# SSTuino.net
KiCad netlist of a schematic drawn in EAGLE
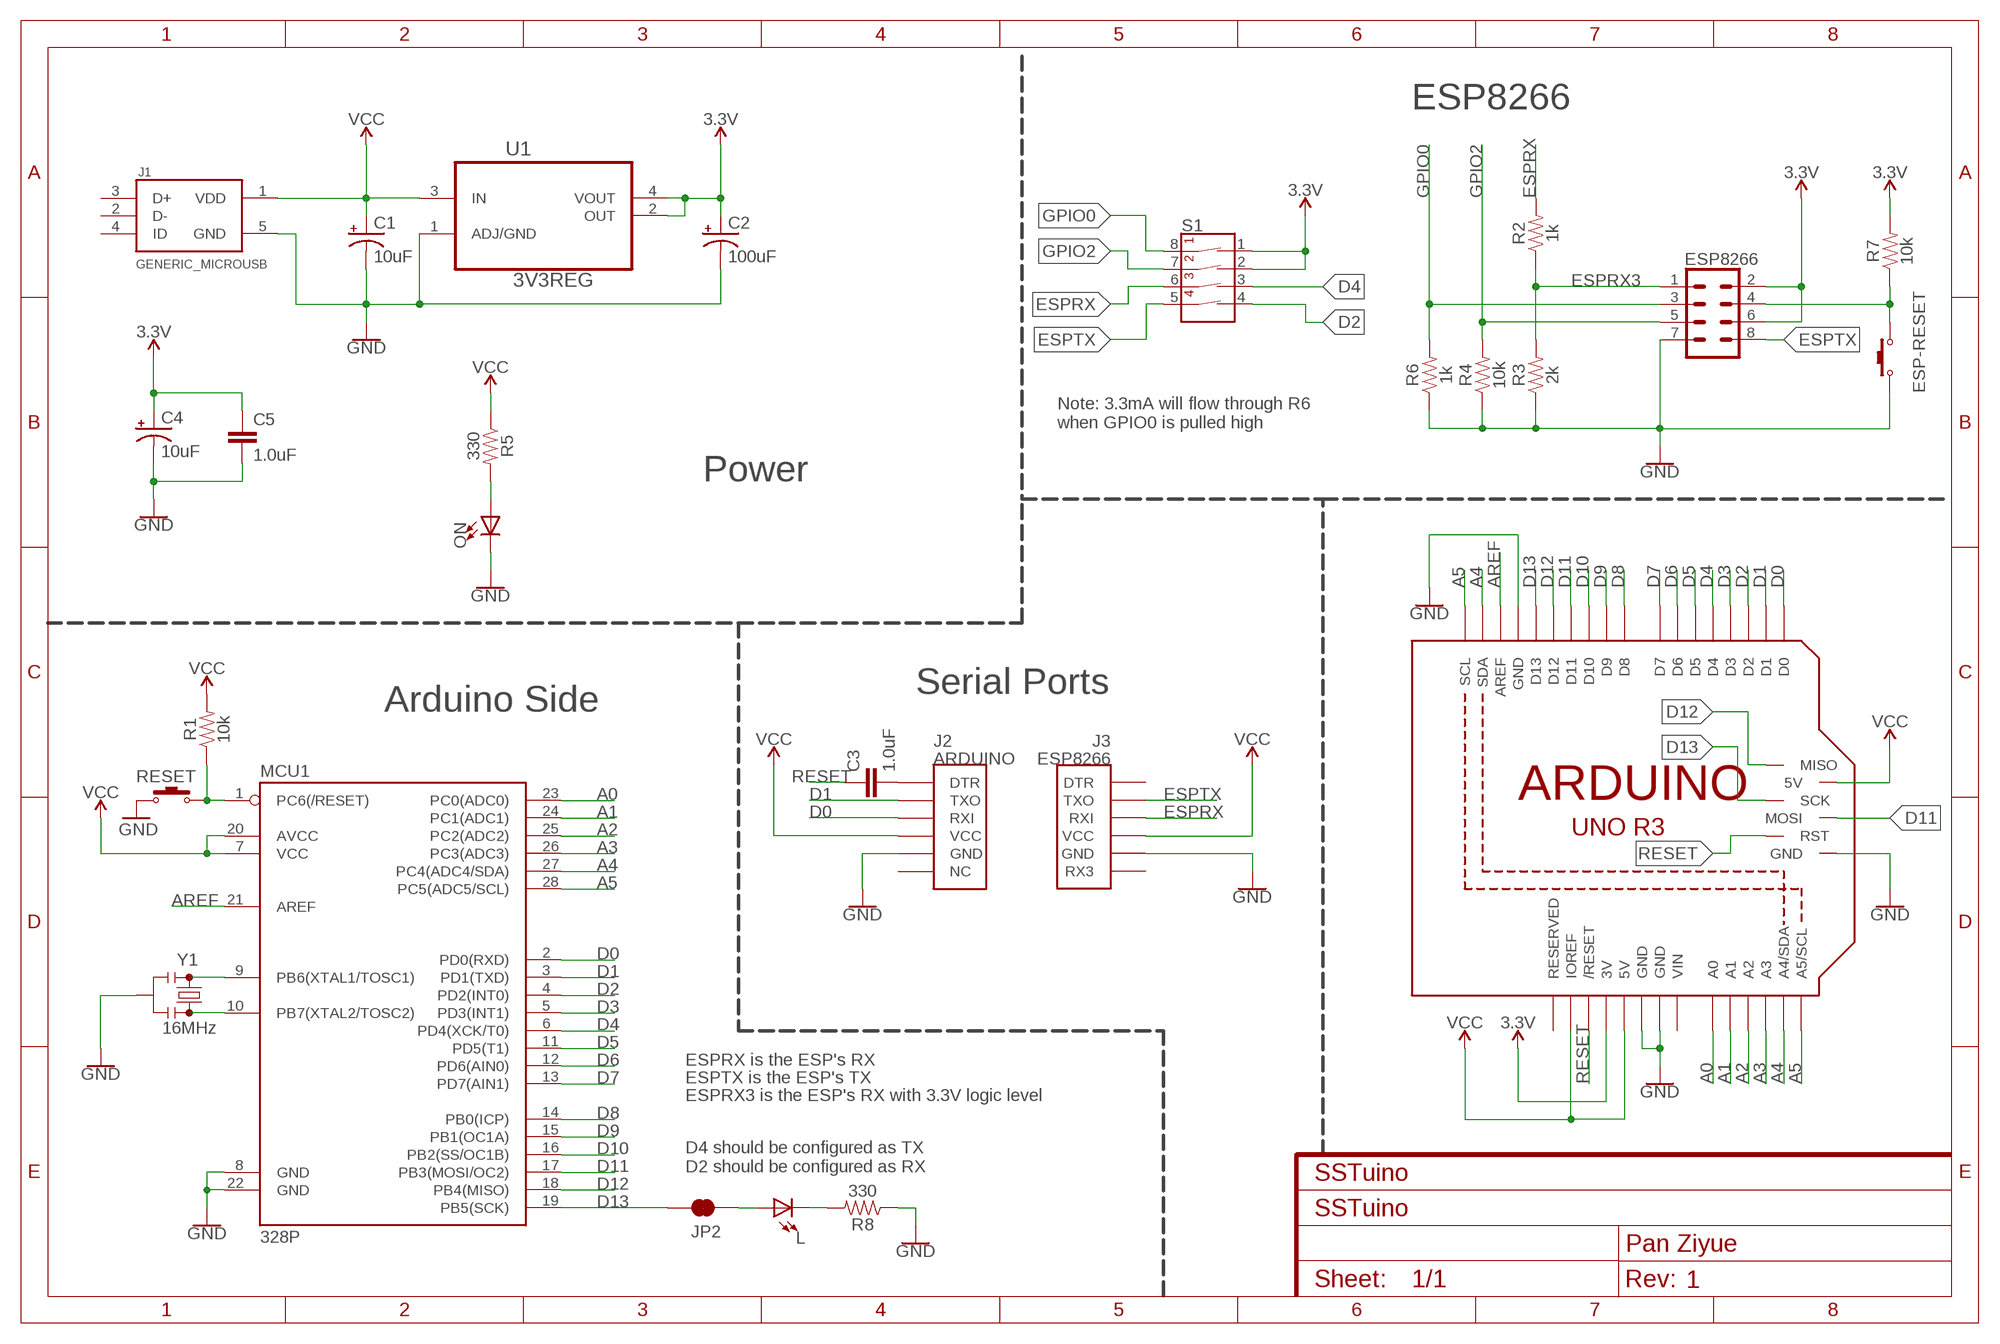
[diagram p0: schematic, sheet 1]

(export (version "E")
  (design (tool "Eeschema 10.0.6"))
  (components
    (comp (ref "C1")
      (value "10uF")
      (footprint "eagle-import:EIA3528")
      (libsource (lib "eagle-import") (part "10UF-POLAR-EIA3528-20V-10%(TANT)"))
    )
    (comp (ref "C2")
      (value "100uF")
      (footprint "eagle-import:PANASONIC_D")
      (libsource (lib "eagle-import") (part "100UF-POLAR-25V-20%(ELEC)"))
    )
    (comp (ref "C3")
      (value "1.0uF")
      (footprint "eagle-import:1206")
      (libsource (lib "eagle-import") (part "1.0UF-1206-50V-10%"))
    )
    (comp (ref "C4")
      (value "10uF")
      (footprint "eagle-import:EIA3216")
      (libsource (lib "eagle-import") (part "10UF-POLAR-EIA3216-16V-10%(TANT)"))
    )
    (comp (ref "C5")
      (value "1.0uF")
      (footprint "eagle-import:1206")
      (fields (field (name "SPICEPREFIX") "C"))
      (libsource (lib "eagle-import") (part "1.0UF-1206-50V-10%"))
    )
    (comp (ref "ESP-RESET")
      (value "SW-PB_(KAN0641)")
      (footprint "eagle-import:S-SP-4N-KAN0641")
      (fields (field (name "MF") "GANGYUAN") (field (name "MPN") "KAN0641-0501B1"))
      (libsource (lib "eagle-import") (part "SW-PB_(KAN0641)"))
    )
    (comp (ref "ESP8266")
      (value "CONN_04X2")
      (footprint "eagle-import:2X4")
      (libsource (lib "eagle-import") (part "CONN_04X2"))
    )
    (comp (ref "J1")
      (value "GENERIC_MICROUSB")
      (footprint "eagle-import:FRAMATOME_10118194-0001LF")
      (fields (field (name "MF") "FCI") (field (name "MP") "10118194-0001LF"))
      (libsource (lib "eagle-import") (part "GENERIC_MICROUSB"))
    )
    (comp (ref "J2")
      (value "ARDUINO")
      (footprint "eagle-import:CP2102_DEVICE_MICROUSB")
      (libsource (lib "eagle-import") (part "CP2102_DEVICEMICROUSB"))
    )
    (comp (ref "J3")
      (value "ESP8266")
      (footprint "eagle-import:CP2102_DEVICE_MICROUSB_ESP8266")
      (libsource (lib "eagle-import") (part "CP2102_DEVICE_ESP8266"))
    )
    (comp (ref "JP2")
      (value "JUMPER-SMT_2_NC_TRACE_SILK")
      (footprint "eagle-import:SMT-JUMPER_2_NC_TRACE_SILK")
      (libsource (lib "eagle-import") (part "JUMPER-SMT_2_NC_TRACE_SILK"))
    )
    (comp (ref "L")
      (value "LED3MM")
      (footprint "eagle-import:LED3MM")
      (libsource (lib "eagle-import") (part "LED3MM"))
    )
    (comp (ref "M1")
      (value "ARDUINO_R3_ICSPSST")
      (footprint "eagle-import:ARDUINOR3_ISCP_SST")
      (libsource (lib "eagle-import") (part "ARDUINO_R3_ICSPSST"))
    )
    (comp (ref "MCU1")
      (value "328P")
      (footprint "eagle-import:DIP28")
      (libsource (lib "eagle-import") (part "ATMEGA328P_PDIP"))
    )
    (comp (ref "ON")
      (value "LED3MM")
      (footprint "eagle-import:LED3MM")
      (libsource (lib "eagle-import") (part "LED3MM"))
    )
    (comp (ref "R1")
      (value "10k")
      (footprint "eagle-import:1206")
      (libsource (lib "eagle-import") (part "RESISTOR1206"))
    )
    (comp (ref "R2")
      (value "1k")
      (footprint "eagle-import:1206")
      (libsource (lib "eagle-import") (part "RESISTOR1206"))
    )
    (comp (ref "R3")
      (value "2k")
      (footprint "eagle-import:1206")
      (libsource (lib "eagle-import") (part "RESISTOR1206"))
    )
    (comp (ref "R4")
      (value "10k")
      (footprint "eagle-import:1206")
      (libsource (lib "eagle-import") (part "RESISTOR1206"))
    )
    (comp (ref "R5")
      (value "330")
      (footprint "eagle-import:1206")
      (libsource (lib "eagle-import") (part "RESISTOR1206"))
    )
    (comp (ref "R6")
      (value "1k")
      (footprint "eagle-import:1206")
      (libsource (lib "eagle-import") (part "RESISTOR1206"))
    )
    (comp (ref "R7")
      (value "10k")
      (footprint "eagle-import:1206")
      (libsource (lib "eagle-import") (part "RESISTOR1206"))
    )
    (comp (ref "R8")
      (value "330")
      (footprint "eagle-import:1206")
      (libsource (lib "eagle-import") (part "RESISTOR1206"))
    )
    (comp (ref "RESET")
      (value "SW-PB_(KAN0641)")
      (footprint "eagle-import:S-SP-4N-KAN0641")
      (fields (field (name "MF") "GANGYUAN") (field (name "MPN") "KAN0641-0501B1"))
      (libsource (lib "eagle-import") (part "SW-PB_(KAN0641)"))
    )
    (comp (ref "S1")
      (value "DIP-04SMD")
      (footprint "eagle-import:DIPSWITCH-04-SMD")
      (fields (field (name "SPICEPREFIX") "X"))
      (libsource (lib "eagle-import") (part "DIP-04SMD"))
    )
    (comp (ref "U1")
      (value "3V3REG")
      (footprint "eagle-import:SOT230P696X180-4N")
      (fields (field (name "MPN") "LM1117MP-3.3"))
      (libsource (lib "eagle-import") (part "LM1117MP-3.3"))
    )
    (comp (ref "Y1")
      (value "16MHz")
      (footprint "eagle-import:RESONATOR-SMD-3.2X1.3")
      (libsource (lib "eagle-import") (part "RESONATOR-16MHZSMD_3.2X1.3"))
    )
  )
  (nets
    (net (code "1") (name "/A0") (class "Default")
      (node (ref "M1") (pin "A0") (pinfunction "A0_A0") (pintype "bidirectional"))
      (node (ref "MCU1") (pin "23") (pinfunction "PC0(ADC0)_23") (pintype "bidirectional"))
    )
    (net (code "2") (name "/A1") (class "Default")
      (node (ref "M1") (pin "A1") (pinfunction "A1_A1") (pintype "bidirectional"))
      (node (ref "MCU1") (pin "24") (pinfunction "PC1(ADC1)_24") (pintype "bidirectional"))
    )
    (net (code "3") (name "/A2") (class "Default")
      (node (ref "M1") (pin "A2") (pinfunction "A2_A2") (pintype "bidirectional"))
      (node (ref "MCU1") (pin "25") (pinfunction "PC2(ADC2)_25") (pintype "bidirectional"))
    )
    (net (code "4") (name "/A3") (class "Default")
      (node (ref "M1") (pin "A3") (pinfunction "A3_A3") (pintype "bidirectional"))
      (node (ref "MCU1") (pin "26") (pinfunction "PC3(ADC3)_26") (pintype "bidirectional"))
    )
    (net (code "5") (name "/A4") (class "Default")
      (node (ref "M1") (pin "A4") (pinfunction "A4/SDA_A4") (pintype "bidirectional"))
      (node (ref "M1") (pin "SDA") (pinfunction "SDA_SDA") (pintype "bidirectional"))
      (node (ref "MCU1") (pin "27") (pinfunction "PC4(ADC4/SDA)_27") (pintype "bidirectional"))
    )
    (net (code "6") (name "/A5") (class "Default")
      (node (ref "M1") (pin "A5") (pinfunction "A5/SCL_A5") (pintype "bidirectional"))
      (node (ref "M1") (pin "SCL") (pinfunction "SCL_SCL") (pintype "bidirectional"))
      (node (ref "MCU1") (pin "28") (pinfunction "PC5(ADC5/SCL)_28") (pintype "bidirectional"))
    )
    (net (code "7") (name "/AREF") (class "Default")
      (node (ref "M1") (pin "AREF") (pinfunction "AREF_AREF") (pintype "bidirectional"))
      (node (ref "MCU1") (pin "21") (pinfunction "AREF_21") (pintype "bidirectional"))
    )
    (net (code "8") (name "/D0") (class "Default")
      (node (ref "J2") (pin "RXI") (pinfunction "RXI_RXI") (pintype "bidirectional"))
      (node (ref "M1") (pin "D0") (pinfunction "D0_D0") (pintype "bidirectional"))
      (node (ref "MCU1") (pin "2") (pinfunction "PD0(RXD)_2") (pintype "bidirectional"))
    )
    (net (code "9") (name "/D1") (class "Default")
      (node (ref "J2") (pin "TXO") (pinfunction "TXO_TXO") (pintype "bidirectional"))
      (node (ref "M1") (pin "D1") (pinfunction "D1_D1") (pintype "bidirectional"))
      (node (ref "MCU1") (pin "3") (pinfunction "PD1(TXD)_3") (pintype "bidirectional"))
    )
    (net (code "10") (name "/D3") (class "Default")
      (node (ref "M1") (pin "D3") (pinfunction "D3_D3") (pintype "bidirectional"))
      (node (ref "MCU1") (pin "5") (pinfunction "PD3(INT1)_5") (pintype "bidirectional"))
    )
    (net (code "11") (name "/D5") (class "Default")
      (node (ref "M1") (pin "D5") (pinfunction "D5_D5") (pintype "bidirectional"))
      (node (ref "MCU1") (pin "11") (pinfunction "PD5(T1)_11") (pintype "bidirectional"))
    )
    (net (code "12") (name "/D6") (class "Default")
      (node (ref "M1") (pin "D6") (pinfunction "D6_D6") (pintype "bidirectional"))
      (node (ref "MCU1") (pin "12") (pinfunction "PD6(AIN0)_12") (pintype "bidirectional"))
    )
    (net (code "13") (name "/D7") (class "Default")
      (node (ref "M1") (pin "D7") (pinfunction "D7_D7") (pintype "bidirectional"))
      (node (ref "MCU1") (pin "13") (pinfunction "PD7(AIN1)_13") (pintype "bidirectional"))
    )
    (net (code "14") (name "/D8") (class "Default")
      (node (ref "M1") (pin "D8") (pinfunction "D8_D8") (pintype "bidirectional"))
      (node (ref "MCU1") (pin "14") (pinfunction "PB0(ICP)_14") (pintype "bidirectional"))
    )
    (net (code "15") (name "/D9") (class "Default")
      (node (ref "M1") (pin "D9") (pinfunction "D9_D9") (pintype "bidirectional"))
      (node (ref "MCU1") (pin "15") (pinfunction "PB1(OC1A)_15") (pintype "bidirectional"))
    )
    (net (code "16") (name "/D10") (class "Default")
      (node (ref "M1") (pin "D10") (pinfunction "D10_D10") (pintype "bidirectional"))
      (node (ref "MCU1") (pin "16") (pinfunction "PB2(SS/OC1B)_16") (pintype "bidirectional"))
    )
    (net (code "17") (name "/ESPRX3") (class "Default")
      (node (ref "ESP8266") (pin "1") (pinfunction "1_1") (pintype "passive"))
      (node (ref "R2") (pin "1") (pinfunction "1_1") (pintype "passive"))
      (node (ref "R3") (pin "2") (pinfunction "2_2") (pintype "passive"))
    )
    (net (code "18") (name "/VIN") (class "Default")
      (node (ref "M1") (pin "VIN") (pinfunction "VIN_VIN") (pintype "power_in"))
    )
    (net (code "19") (name "3.3V") (class "Default")
      (node (ref "C2") (pin "+") (pinfunction "+_+") (pintype "passive"))
      (node (ref "C4") (pin "+") (pinfunction "+_+") (pintype "passive"))
      (node (ref "C5") (pin "1") (pinfunction "1_1") (pintype "passive"))
      (node (ref "ESP8266") (pin "2") (pinfunction "2_2") (pintype "passive"))
      (node (ref "ESP8266") (pin "6") (pinfunction "6_6") (pintype "passive"))
      (node (ref "M1") (pin "3V") (pinfunction "3V_3V") (pintype "power_in"))
      (node (ref "R7") (pin "2") (pinfunction "2_2") (pintype "passive"))
      (node (ref "S1") (pin "1") (pinfunction "1A_1") (pintype "bidirectional"))
      (node (ref "S1") (pin "2") (pinfunction "2A_2") (pintype "bidirectional"))
      (node (ref "U1") (pin "2") (pinfunction "OUT_2") (pintype "output"))
      (node (ref "U1") (pin "4") (pinfunction "VOUT_4") (pintype "output"))
    )
    (net (code "20") (name "D2") (class "Default")
      (node (ref "M1") (pin "D2") (pinfunction "D2_D2") (pintype "bidirectional"))
      (node (ref "MCU1") (pin "4") (pinfunction "PD2(INT0)_4") (pintype "bidirectional"))
      (node (ref "S1") (pin "4") (pinfunction "4A_4") (pintype "bidirectional"))
    )
    (net (code "21") (name "D4") (class "Default")
      (node (ref "M1") (pin "D4") (pinfunction "D4_D4") (pintype "bidirectional"))
      (node (ref "MCU1") (pin "6") (pinfunction "PD4(XCK/T0)_6") (pintype "bidirectional"))
      (node (ref "S1") (pin "3") (pinfunction "3A_3") (pintype "bidirectional"))
    )
    (net (code "22") (name "D11") (class "Default")
      (node (ref "M1") (pin "D11") (pinfunction "D11_D11") (pintype "bidirectional"))
      (node (ref "M1") (pin "MOSI") (pinfunction "MOSI_MOSI") (pintype "passive"))
      (node (ref "MCU1") (pin "17") (pinfunction "PB3(MOSI/OC2)_17") (pintype "bidirectional"))
    )
    (net (code "23") (name "D12") (class "Default")
      (node (ref "M1") (pin "D12") (pinfunction "D12_D12") (pintype "bidirectional"))
      (node (ref "M1") (pin "MISO") (pinfunction "MISO_MISO") (pintype "passive"))
      (node (ref "MCU1") (pin "18") (pinfunction "PB4(MISO)_18") (pintype "bidirectional"))
    )
    (net (code "24") (name "D13") (class "Default")
      (node (ref "JP2") (pin "2") (pinfunction "2_2") (pintype "passive"))
      (node (ref "M1") (pin "D13") (pinfunction "D13_D13") (pintype "bidirectional"))
      (node (ref "M1") (pin "SCK") (pinfunction "SCK_SCK") (pintype "passive"))
      (node (ref "MCU1") (pin "19") (pinfunction "PB5(SCK)_19") (pintype "bidirectional"))
    )
    (net (code "25") (name "ESPRX") (class "Default")
      (node (ref "J3") (pin "P$4") (pinfunction "RXI_P$4") (pintype "bidirectional"))
      (node (ref "R2") (pin "2") (pinfunction "2_2") (pintype "passive"))
      (node (ref "S1") (pin "6") (pinfunction "3B_6") (pintype "bidirectional"))
    )
    (net (code "26") (name "ESPTX") (class "Default")
      (node (ref "ESP8266") (pin "8") (pinfunction "8_8") (pintype "passive"))
      (node (ref "J3") (pin "P$3") (pinfunction "TXO_P$3") (pintype "bidirectional"))
      (node (ref "S1") (pin "5") (pinfunction "4B_5") (pintype "bidirectional"))
    )
    (net (code "27") (name "GND") (class "Default")
      (node (ref "C1") (pin "C") (pinfunction "-_C") (pintype "passive"))
      (node (ref "C2") (pin "-") (pinfunction "-_-") (pintype "passive"))
      (node (ref "C4") (pin "-") (pinfunction "-_-") (pintype "passive"))
      (node (ref "C5") (pin "2") (pinfunction "2_2") (pintype "passive"))
      (node (ref "ESP-RESET") (pin "1") (pinfunction "1_1") (pintype "passive"))
      (node (ref "ESP-RESET") (pin "2") (pinfunction "1_2") (pintype "passive"))
      (node (ref "ESP8266") (pin "7") (pinfunction "7_7") (pintype "passive"))
      (node (ref "J1") (pin "5") (pinfunction "GND_5") (pintype "power_in"))
      (node (ref "J2") (pin "GND") (pinfunction "GND_GND") (pintype "bidirectional"))
      (node (ref "J3") (pin "P$5") (pinfunction "GND_P$5") (pintype "bidirectional"))
      (node (ref "M1") (pin "GND") (pinfunction "GND_GND") (pintype "power_in"))
      (node (ref "M1") (pin "GND@1") (pinfunction "GND_GND@1") (pintype "power_in"))
      (node (ref "M1") (pin "GND@2") (pinfunction "GND_GND@2") (pintype "power_in"))
      (node (ref "M1") (pin "GND@3") (pinfunction "GND_GND@3") (pintype "passive"))
      (node (ref "MCU1") (pin "22") (pinfunction "GND_22") (pintype "bidirectional"))
      (node (ref "MCU1") (pin "8") (pinfunction "GND_8") (pintype "bidirectional"))
      (node (ref "ON") (pin "K") (pinfunction "C_K") (pintype "passive"))
      (node (ref "R3") (pin "1") (pinfunction "1_1") (pintype "passive"))
      (node (ref "R4") (pin "1") (pinfunction "1_1") (pintype "passive"))
      (node (ref "R6") (pin "1") (pinfunction "1_1") (pintype "passive"))
      (node (ref "R8") (pin "1") (pinfunction "1_1") (pintype "passive"))
      (node (ref "RESET") (pin "1") (pinfunction "1_1") (pintype "passive"))
      (node (ref "RESET") (pin "2") (pinfunction "1_2") (pintype "passive"))
      (node (ref "U1") (pin "1") (pinfunction "ADJ/GND_1") (pintype "passive"))
      (node (ref "Y1") (pin "2") (pinfunction "2_2") (pintype "passive"))
    )
    (net (code "28") (name "GPIO0") (class "Default")
      (node (ref "ESP8266") (pin "3") (pinfunction "3_3") (pintype "passive"))
      (node (ref "R6") (pin "2") (pinfunction "2_2") (pintype "passive"))
      (node (ref "S1") (pin "8") (pinfunction "1B_8") (pintype "bidirectional"))
    )
    (net (code "29") (name "GPIO2") (class "Default")
      (node (ref "ESP8266") (pin "5") (pinfunction "5_5") (pintype "passive"))
      (node (ref "R4") (pin "2") (pinfunction "2_2") (pintype "passive"))
      (node (ref "S1") (pin "7") (pinfunction "2B_7") (pintype "bidirectional"))
    )
    (net (code "30") (name "Net-(C3-Pad2)") (class "Default")
      (node (ref "C3") (pin "2") (pinfunction "2_2") (pintype "passive"))
      (node (ref "J2") (pin "DTR") (pinfunction "DTR_DTR") (pintype "bidirectional"))
    )
    (net (code "31") (name "Net-(ESP-RESET-2-Pad3)") (class "Default")
      (node (ref "ESP-RESET") (pin "3") (pinfunction "2_3") (pintype "passive"))
      (node (ref "ESP-RESET") (pin "4") (pinfunction "2_4") (pintype "passive"))
      (node (ref "ESP8266") (pin "4") (pinfunction "4_4") (pintype "passive"))
      (node (ref "R7") (pin "1") (pinfunction "1_1") (pintype "passive"))
    )
    (net (code "32") (name "Net-(JP2-Pad1)") (class "Default")
      (node (ref "JP2") (pin "1") (pinfunction "1_1") (pintype "passive"))
      (node (ref "L") (pin "A") (pinfunction "A_A") (pintype "passive"))
    )
    (net (code "33") (name "Net-(L-C)") (class "Default")
      (node (ref "L") (pin "K") (pinfunction "C_K") (pintype "passive"))
      (node (ref "R8") (pin "2") (pinfunction "2_2") (pintype "passive"))
    )
    (net (code "34") (name "Net-(MCU1-PB6(XTAL1{slash}TOSC1))") (class "Default")
      (node (ref "MCU1") (pin "9") (pinfunction "PB6(XTAL1/TOSC1)_9") (pintype "bidirectional"))
      (node (ref "Y1") (pin "1") (pinfunction "1_1") (pintype "passive"))
    )
    (net (code "35") (name "Net-(MCU1-PB7(XTAL2{slash}TOSC2))") (class "Default")
      (node (ref "MCU1") (pin "10") (pinfunction "PB7(XTAL2/TOSC2)_10") (pintype "bidirectional"))
      (node (ref "Y1") (pin "3") (pinfunction "3_3") (pintype "passive"))
    )
    (net (code "36") (name "Net-(ON-PadA)") (class "Default")
      (node (ref "ON") (pin "A") (pinfunction "A_A") (pintype "passive"))
      (node (ref "R5") (pin "2") (pinfunction "2_2") (pintype "passive"))
    )
    (net (code "37") (name "RESET") (class "Default")
      (node (ref "C3") (pin "1") (pinfunction "1_1") (pintype "passive"))
      (node (ref "M1") (pin "RESET") (pinfunction "/RESET_RESET") (pintype "bidirectional"))
      (node (ref "M1") (pin "RESET_ICSP") (pinfunction "RST_RESET_ICSP") (pintype "passive"))
      (node (ref "MCU1") (pin "1") (pinfunction "PC6(/RESET)_1") (pintype "bidirectional"))
      (node (ref "R1") (pin "1") (pinfunction "1_1") (pintype "passive"))
      (node (ref "RESET") (pin "3") (pinfunction "2_3") (pintype "passive"))
      (node (ref "RESET") (pin "4") (pinfunction "2_4") (pintype "passive"))
    )
    (net (code "38") (name "VCC") (class "Default")
      (node (ref "C1") (pin "A") (pinfunction "+_A") (pintype "passive"))
      (node (ref "J1") (pin "1") (pinfunction "VDD_1") (pintype "power_in"))
      (node (ref "J2") (pin "5V") (pinfunction "VCC_5V") (pintype "bidirectional"))
      (node (ref "J3") (pin "P$6") (pinfunction "VCC_P$6") (pintype "bidirectional"))
      (node (ref "M1") (pin "5V") (pinfunction "5V_5V") (pintype "power_in"))
      (node (ref "M1") (pin "5V_ICSP") (pinfunction "5V_5V_ICSP") (pintype "passive"))
      (node (ref "M1") (pin "IOREF") (pinfunction "IOREF_IOREF") (pintype "output"))
      (node (ref "MCU1") (pin "20") (pinfunction "AVCC_20") (pintype "bidirectional"))
      (node (ref "MCU1") (pin "7") (pinfunction "VCC_7") (pintype "bidirectional"))
      (node (ref "R1") (pin "2") (pinfunction "2_2") (pintype "passive"))
      (node (ref "R5") (pin "1") (pinfunction "1_1") (pintype "passive"))
      (node (ref "U1") (pin "3") (pinfunction "IN_3") (pintype "input"))
    )
    (net (code "39") (name "unconnected-(J1-D+-Pad3)") (class "Default")
      (node (ref "J1") (pin "3") (pinfunction "D+_3") (pintype "bidirectional"))
    )
    (net (code "40") (name "unconnected-(J1-D--Pad2)") (class "Default")
      (node (ref "J1") (pin "2") (pinfunction "D-_2") (pintype "bidirectional"))
    )
    (net (code "41") (name "unconnected-(J1-ID-Pad4)") (class "Default")
      (node (ref "J1") (pin "4") (pinfunction "ID_4") (pintype "passive"))
    )
    (net (code "42") (name "unconnected-(J2-NC-Pad3V)") (class "Default")
      (node (ref "J2") (pin "3V") (pinfunction "NC_3V") (pintype "bidirectional"))
    )
    (net (code "43") (name "unconnected-(J3-DTR-PadP$2)") (class "Default")
      (node (ref "J3") (pin "P$2") (pinfunction "DTR_P$2") (pintype "bidirectional"))
    )
    (net (code "44") (name "unconnected-(J3-RX3-PadP$1)") (class "Default")
      (node (ref "J3") (pin "P$1") (pinfunction "RX3_P$1") (pintype "bidirectional"))
    )
    (net (code "45") (name "unconnected-(M1-PadRESERVED)") (class "Default")
      (node (ref "M1") (pin "RESERVED") (pinfunction "RESERVED_RESERVED") (pintype "no_connect"))
    )
  )
)
